# Sheet_1.net
KiCad netlist of a schematic drawn in EasyEDA
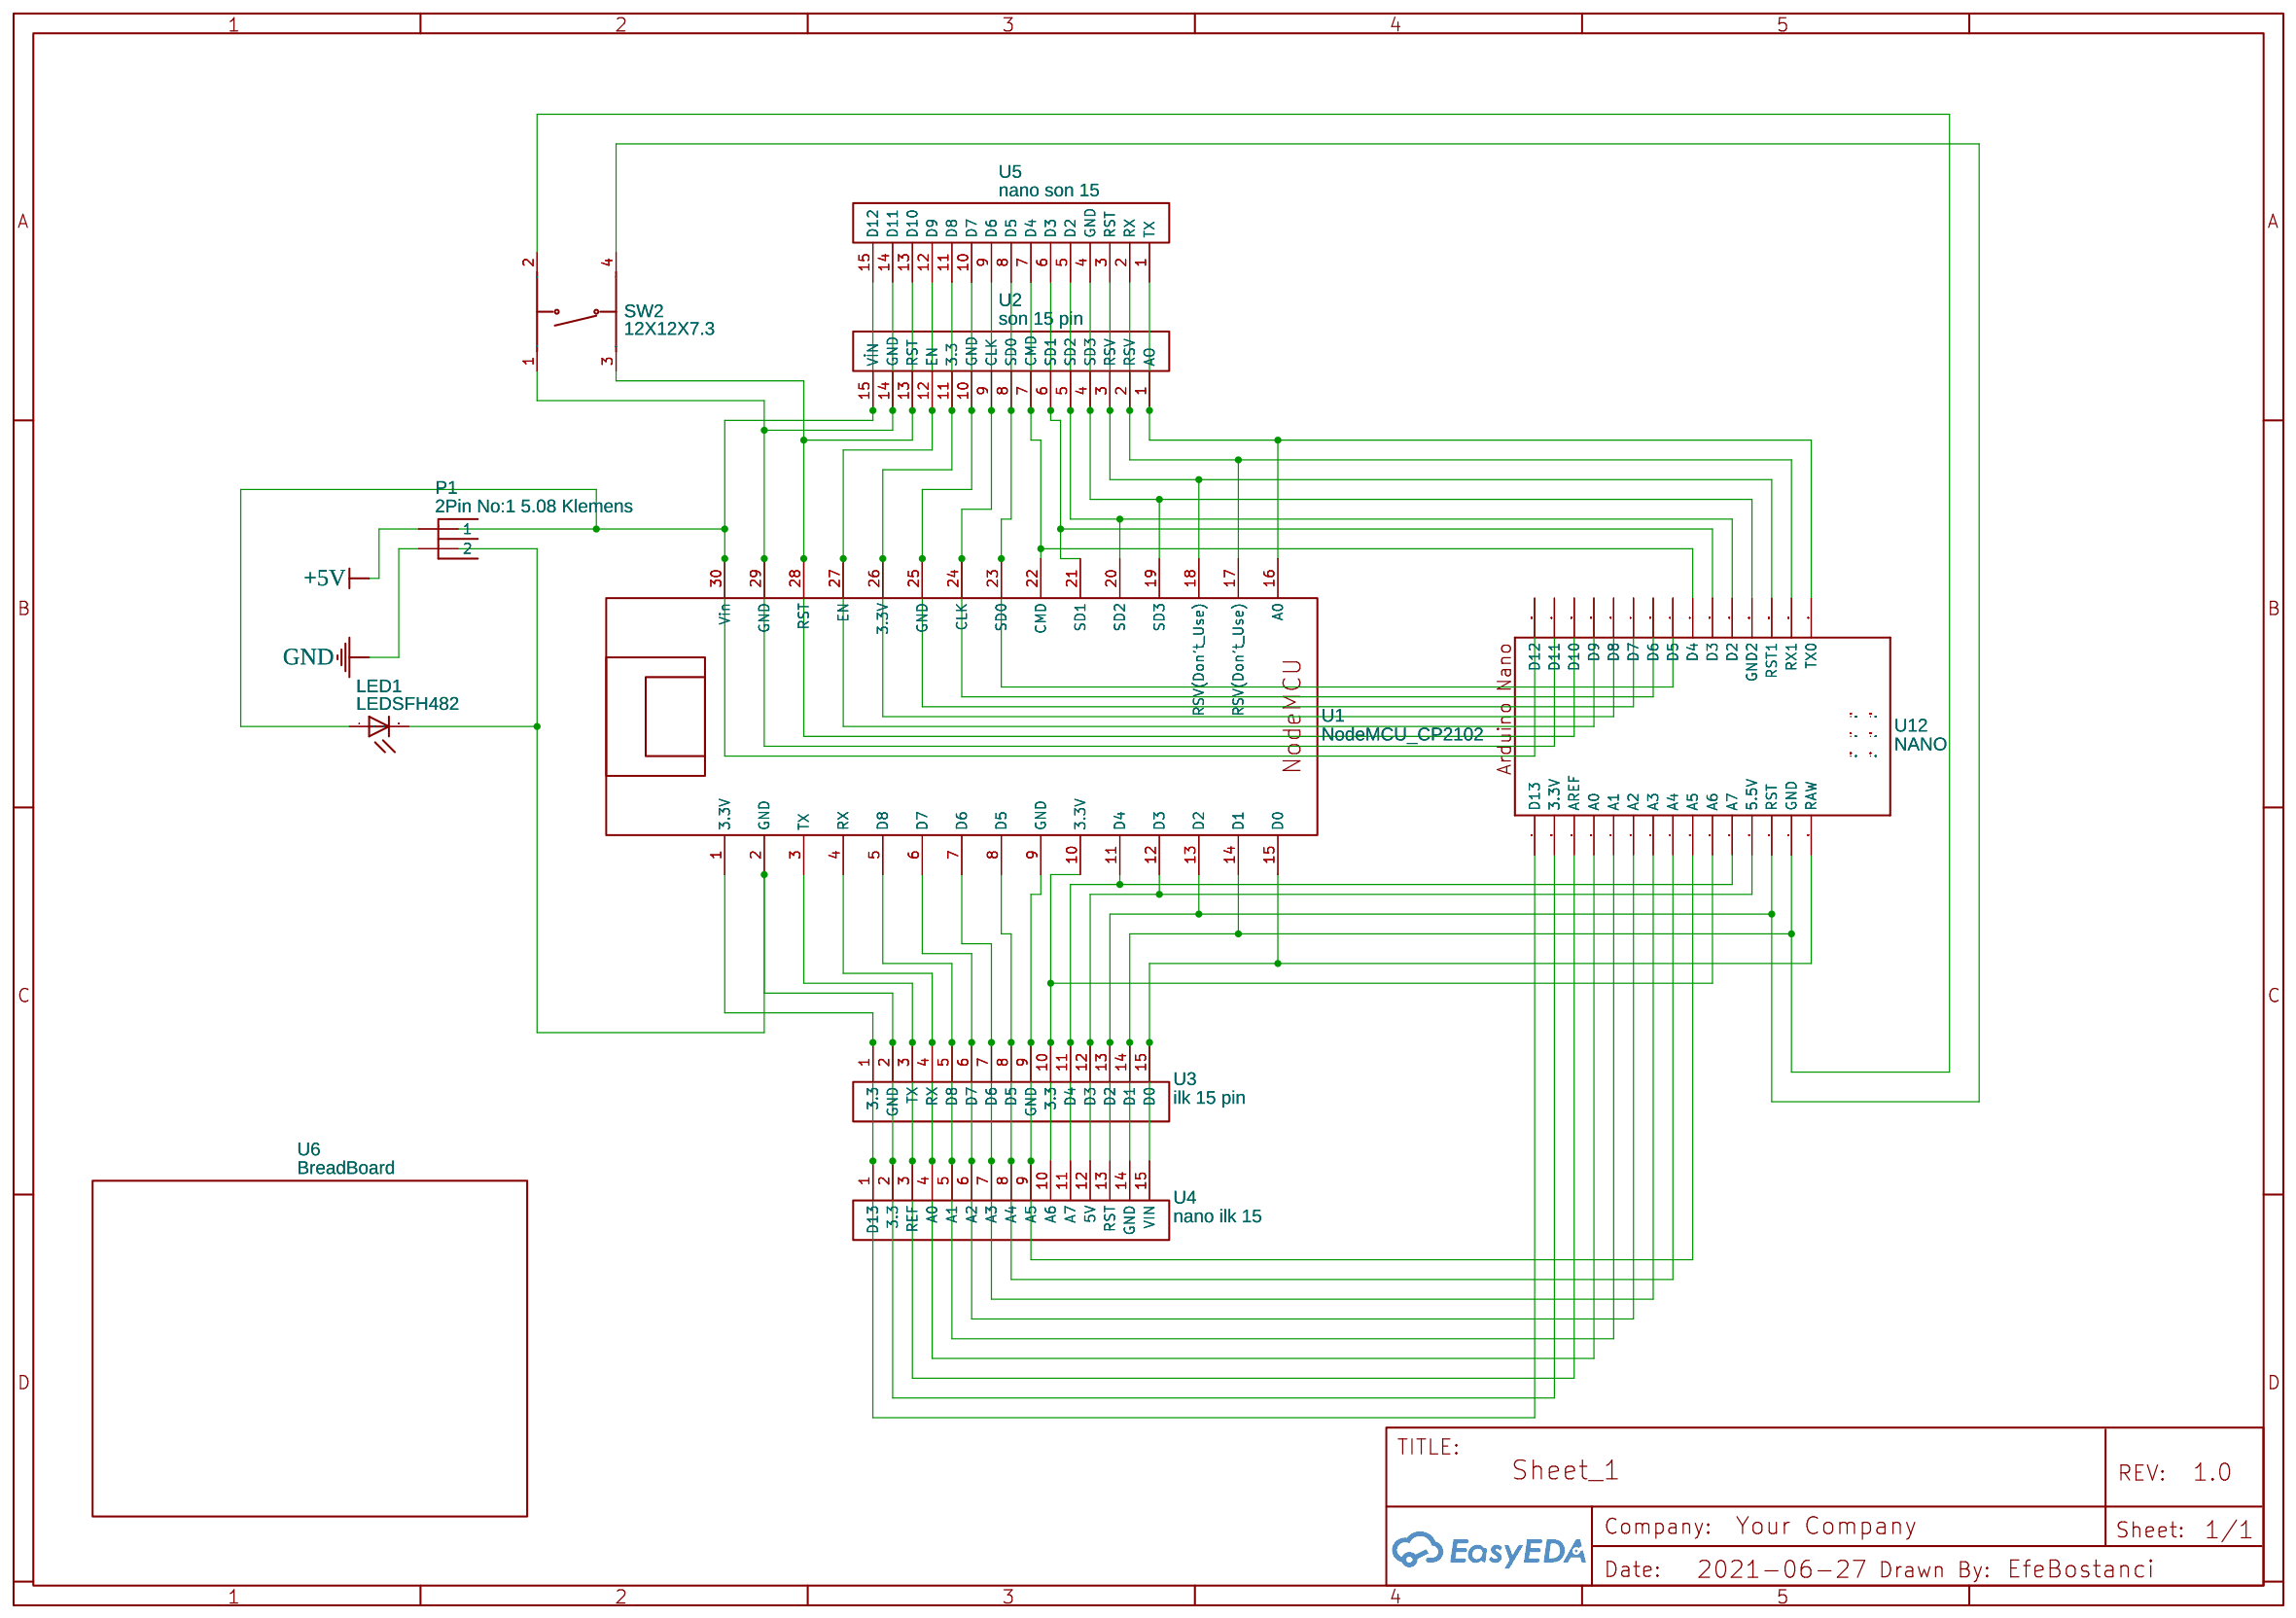
[diagram p0: schematic sheet]

(export (version "E")
  (design (tool "Eeschema 10.0.6"))
  (components
    (comp (ref "LED1") (value "LEDSFH482") (libsource (lib "") (part "LEDSFH482")))
    (comp (ref "P1")
      (value "2Pin No:1 5.08 Klemens")
      (fields (field (name "BOM_Manufacturer Part") "Terminal 2Pol 5,08mm"))
      (libsource (lib "") (part "2Pin No{colon}1 5.08 Klemens"))
    )
    (comp (ref "SW2")
      (value "12X12X7.3")
      (fields (field (name "BOM_Supplier Part") "C10861"))
      (libsource (lib "") (part "12X12X7.3"))
    )
    (comp (ref "U1") (value "NodeMCU_CP2102") (libsource (lib "") (part "NodeMCU_CP2102")))
    (comp (ref "U2") (value "son 15 pin") (libsource (lib "") (part "15 pin_1")))
    (comp (ref "U3") (value "ilk 15 pin") (libsource (lib "") (part "15 pin_3")))
    (comp (ref "U4") (value "nano ilk 15") (libsource (lib "") (part "15 pin")))
    (comp (ref "U5") (value "nano son 15") (libsource (lib "") (part "15 pin_2")))
    (comp (ref "U6") (value "BreadBoard") (libsource (lib "") (part "BreadBoard")))
    (comp (ref "U12") (value "NANO") (libsource (lib "") (part "NANO")))
  )
  (nets
    (net (code "1") (name "+5V") (class "Default")
      (node (ref "P1") (pin "1") (pinfunction "1_1") (pintype "unspecified"))
    )
    (net (code "2") (name "GND") (class "Default")
      (node (ref "P1") (pin "2") (pinfunction "2_2") (pintype "unspecified"))
    )
    (net (code "3") (name "Net-(LED1-C)") (class "Default")
      (node (ref "LED1") (pin "K") (pinfunction "C_K") (pintype "unspecified"))
      (node (ref "U1") (pin "2") (pinfunction "GND_2") (pintype "unspecified"))
      (node (ref "U12") (pin "3.3V") (pinfunction "3.3V_3.3V") (pintype "unspecified"))
      (node (ref "U3") (pin "2") (pinfunction "GND_2") (pintype "unspecified"))
      (node (ref "U4") (pin "2") (pinfunction "3.3_2") (pintype "unspecified"))
    )
    (net (code "4") (name "Net-(U1-A0)") (class "Default")
      (node (ref "U1") (pin "16") (pinfunction "A0_16") (pintype "unspecified"))
      (node (ref "U12") (pin "TX0") (pinfunction "TX0_TX0") (pintype "unspecified"))
      (node (ref "U2") (pin "1") (pinfunction "AO_1") (pintype "unspecified"))
      (node (ref "U5") (pin "1") (pinfunction "TX_1") (pintype "unspecified"))
    )
    (net (code "5") (name "Net-(U1-CLK)") (class "Default")
      (node (ref "U1") (pin "24") (pinfunction "CLK_24") (pintype "unspecified"))
      (node (ref "U12") (pin "D6") (pinfunction "D6_D6") (pintype "unspecified"))
      (node (ref "U2") (pin "9") (pinfunction "CLK_9") (pintype "unspecified"))
      (node (ref "U5") (pin "9") (pinfunction "D6_9") (pintype "unspecified"))
    )
    (net (code "6") (name "Net-(U1-CMD)") (class "Default")
      (node (ref "U1") (pin "22") (pinfunction "CMD_22") (pintype "unspecified"))
      (node (ref "U12") (pin "D4") (pinfunction "D4_D4") (pintype "unspecified"))
      (node (ref "U2") (pin "7") (pinfunction "CMD_7") (pintype "unspecified"))
      (node (ref "U5") (pin "7") (pinfunction "D4_7") (pintype "unspecified"))
    )
    (net (code "7") (name "Net-(U1-D0)") (class "Default")
      (node (ref "U1") (pin "15") (pinfunction "D0_15") (pintype "unspecified"))
      (node (ref "U12") (pin "RAW") (pinfunction "RAW_RAW") (pintype "unspecified"))
      (node (ref "U3") (pin "15") (pinfunction "D0_15") (pintype "unspecified"))
      (node (ref "U4") (pin "15") (pinfunction "VIN_15") (pintype "unspecified"))
    )
    (net (code "8") (name "Net-(U1-D1)") (class "Default")
      (node (ref "SW2") (pin "2") (pinfunction "2_2") (pintype "unspecified"))
      (node (ref "U1") (pin "14") (pinfunction "D1_14") (pintype "unspecified"))
      (node (ref "U12") (pin "GND") (pinfunction "GND_GND") (pintype "unspecified"))
      (node (ref "U3") (pin "14") (pinfunction "D1_14") (pintype "unspecified"))
      (node (ref "U4") (pin "14") (pinfunction "GND_14") (pintype "unspecified"))
    )
    (net (code "9") (name "Net-(U1-D2)") (class "Default")
      (node (ref "SW2") (pin "4") (pinfunction "4_4") (pintype "unspecified"))
      (node (ref "U1") (pin "13") (pinfunction "D2_13") (pintype "unspecified"))
      (node (ref "U12") (pin "RST") (pinfunction "RST_RST") (pintype "unspecified"))
      (node (ref "U3") (pin "13") (pinfunction "D2_13") (pintype "unspecified"))
      (node (ref "U4") (pin "13") (pinfunction "RST_13") (pintype "unspecified"))
    )
    (net (code "10") (name "Net-(U1-D3)") (class "Default")
      (node (ref "U1") (pin "12") (pinfunction "D3_12") (pintype "unspecified"))
      (node (ref "U12") (pin "5V") (pinfunction "5.5V_5V") (pintype "unspecified"))
      (node (ref "U3") (pin "12") (pinfunction "D3_12") (pintype "unspecified"))
      (node (ref "U4") (pin "12") (pinfunction "5V_12") (pintype "unspecified"))
    )
    (net (code "11") (name "Net-(U1-D4)") (class "Default")
      (node (ref "U1") (pin "11") (pinfunction "D4_11") (pintype "unspecified"))
      (node (ref "U12") (pin "A7") (pinfunction "A7_A7") (pintype "unspecified"))
      (node (ref "U3") (pin "11") (pinfunction "D4_11") (pintype "unspecified"))
      (node (ref "U4") (pin "11") (pinfunction "A7_11") (pintype "unspecified"))
    )
    (net (code "12") (name "Net-(U1-D5)") (class "Default")
      (node (ref "U1") (pin "8") (pinfunction "D5_8") (pintype "unspecified"))
      (node (ref "U12") (pin "A4") (pinfunction "A4_A4") (pintype "unspecified"))
      (node (ref "U3") (pin "8") (pinfunction "D5_8") (pintype "unspecified"))
      (node (ref "U4") (pin "8") (pinfunction "A4_8") (pintype "unspecified"))
    )
    (net (code "13") (name "Net-(U1-D6)") (class "Default")
      (node (ref "U1") (pin "7") (pinfunction "D6_7") (pintype "unspecified"))
      (node (ref "U12") (pin "A3") (pinfunction "A3_A3") (pintype "unspecified"))
      (node (ref "U3") (pin "7") (pinfunction "D6_7") (pintype "unspecified"))
      (node (ref "U4") (pin "7") (pinfunction "A3_7") (pintype "unspecified"))
    )
    (net (code "14") (name "Net-(U1-D7)") (class "Default")
      (node (ref "U1") (pin "6") (pinfunction "D7_6") (pintype "unspecified"))
      (node (ref "U12") (pin "A2") (pinfunction "A2_A2") (pintype "unspecified"))
      (node (ref "U3") (pin "6") (pinfunction "D7_6") (pintype "unspecified"))
      (node (ref "U4") (pin "6") (pinfunction "A2_6") (pintype "unspecified"))
    )
    (net (code "15") (name "Net-(U1-D8)") (class "Default")
      (node (ref "U1") (pin "5") (pinfunction "D8_5") (pintype "unspecified"))
      (node (ref "U12") (pin "A1") (pinfunction "A1_A1") (pintype "unspecified"))
      (node (ref "U3") (pin "5") (pinfunction "D8_5") (pintype "unspecified"))
      (node (ref "U4") (pin "5") (pinfunction "A1_5") (pintype "unspecified"))
    )
    (net (code "16") (name "Net-(U1-EN)") (class "Default")
      (node (ref "U1") (pin "27") (pinfunction "EN_27") (pintype "unspecified"))
      (node (ref "U12") (pin "D9") (pinfunction "D9_D9") (pintype "unspecified"))
      (node (ref "U2") (pin "12") (pinfunction "EN_12") (pintype "unspecified"))
      (node (ref "U5") (pin "12") (pinfunction "D9_12") (pintype "unspecified"))
    )
    (net (code "17") (name "Net-(U1-RST)") (class "Default")
      (node (ref "SW2") (pin "3") (pinfunction "3_3") (pintype "unspecified"))
      (node (ref "U1") (pin "28") (pinfunction "RST_28") (pintype "unspecified"))
      (node (ref "U12") (pin "D10") (pinfunction "D10_D10") (pintype "unspecified"))
      (node (ref "U2") (pin "13") (pinfunction "RST_13") (pintype "unspecified"))
      (node (ref "U5") (pin "13") (pinfunction "D10_13") (pintype "unspecified"))
    )
    (net (code "18") (name "Net-(U1-RX)") (class "Default")
      (node (ref "U1") (pin "4") (pinfunction "RX_4") (pintype "unspecified"))
      (node (ref "U12") (pin "A0") (pinfunction "A0_A0") (pintype "unspecified"))
      (node (ref "U3") (pin "4") (pinfunction "RX_4") (pintype "unspecified"))
      (node (ref "U4") (pin "4") (pinfunction "A0_4") (pintype "unspecified"))
    )
    (net (code "19") (name "Net-(U1-SD0)") (class "Default")
      (node (ref "U1") (pin "23") (pinfunction "SD0_23") (pintype "unspecified"))
      (node (ref "U12") (pin "D5") (pinfunction "D5_D5") (pintype "unspecified"))
      (node (ref "U2") (pin "8") (pinfunction "SD0_8") (pintype "unspecified"))
      (node (ref "U5") (pin "8") (pinfunction "D5_8") (pintype "unspecified"))
    )
    (net (code "20") (name "Net-(U1-SD1)") (class "Default")
      (node (ref "U1") (pin "21") (pinfunction "SD1_21") (pintype "unspecified"))
      (node (ref "U12") (pin "D3") (pinfunction "D3_D3") (pintype "unspecified"))
      (node (ref "U2") (pin "6") (pinfunction "SD1_6") (pintype "unspecified"))
      (node (ref "U5") (pin "6") (pinfunction "D3_6") (pintype "unspecified"))
    )
    (net (code "21") (name "Net-(U1-SD2)") (class "Default")
      (node (ref "U1") (pin "20") (pinfunction "SD2_20") (pintype "unspecified"))
      (node (ref "U12") (pin "D2") (pinfunction "D2_D2") (pintype "unspecified"))
      (node (ref "U2") (pin "5") (pinfunction "SD2_5") (pintype "unspecified"))
      (node (ref "U5") (pin "5") (pinfunction "D2_5") (pintype "unspecified"))
    )
    (net (code "22") (name "Net-(U1-SD3)") (class "Default")
      (node (ref "U1") (pin "19") (pinfunction "SD3_19") (pintype "unspecified"))
      (node (ref "U12") (pin "GND1") (pinfunction "GND2_GND1") (pintype "unspecified"))
      (node (ref "U2") (pin "4") (pinfunction "SD3_4") (pintype "unspecified"))
      (node (ref "U5") (pin "4") (pinfunction "GND_4") (pintype "unspecified"))
    )
    (net (code "23") (name "Net-(U1-TX)") (class "Default")
      (node (ref "U1") (pin "3") (pinfunction "TX_3") (pintype "unspecified"))
      (node (ref "U12") (pin "AREF") (pinfunction "AREF_AREF") (pintype "unspecified"))
      (node (ref "U3") (pin "3") (pinfunction "TX_3") (pintype "unspecified"))
      (node (ref "U4") (pin "3") (pinfunction "REF_3") (pintype "unspecified"))
    )
    (net (code "24") (name "Net-(U1-Vin)") (class "Default")
      (node (ref "LED1") (pin "A") (pinfunction "A_A") (pintype "unspecified"))
      (node (ref "U1") (pin "30") (pinfunction "Vin_30") (pintype "unspecified"))
      (node (ref "U12") (pin "D12") (pinfunction "D12_D12") (pintype "unspecified"))
      (node (ref "U2") (pin "15") (pinfunction "VİN_15") (pintype "unspecified"))
      (node (ref "U5") (pin "15") (pinfunction "D12_15") (pintype "unspecified"))
    )
    (net (code "25") (name "Net-(U2-3.3)") (class "Default")
      (node (ref "U1") (pin "26") (pinfunction "3.3V_26") (pintype "unspecified"))
      (node (ref "U12") (pin "D8") (pinfunction "D8_D8") (pintype "unspecified"))
      (node (ref "U2") (pin "11") (pinfunction "3.3_11") (pintype "unspecified"))
      (node (ref "U5") (pin "11") (pinfunction "D8_11") (pintype "unspecified"))
    )
    (net (code "26") (name "Net-(U4-A5)") (class "Default")
      (node (ref "U1") (pin "9") (pinfunction "GND_9") (pintype "unspecified"))
      (node (ref "U12") (pin "A5") (pinfunction "A5_A5") (pintype "unspecified"))
      (node (ref "U3") (pin "9") (pinfunction "GND_9") (pintype "unspecified"))
      (node (ref "U4") (pin "9") (pinfunction "A5_9") (pintype "unspecified"))
    )
    (net (code "27") (name "Net-(U4-A6)") (class "Default")
      (node (ref "U1") (pin "10") (pinfunction "3.3V_10") (pintype "unspecified"))
      (node (ref "U12") (pin "A6") (pinfunction "A6_A6") (pintype "unspecified"))
      (node (ref "U3") (pin "10") (pinfunction "3.3_10") (pintype "unspecified"))
      (node (ref "U4") (pin "10") (pinfunction "A6_10") (pintype "unspecified"))
    )
    (net (code "28") (name "Net-(U4-D13)") (class "Default")
      (node (ref "U1") (pin "1") (pinfunction "3.3V_1") (pintype "unspecified"))
      (node (ref "U12") (pin "D13") (pinfunction "D13_D13") (pintype "unspecified"))
      (node (ref "U3") (pin "1") (pinfunction "3.3_1") (pintype "unspecified"))
      (node (ref "U4") (pin "1") (pinfunction "D13_1") (pintype "unspecified"))
    )
    (net (code "29") (name "Net-(U5-D7)") (class "Default")
      (node (ref "U1") (pin "25") (pinfunction "GND_25") (pintype "unspecified"))
      (node (ref "U12") (pin "D7") (pinfunction "D7_D7") (pintype "unspecified"))
      (node (ref "U2") (pin "10") (pinfunction "GND_10") (pintype "unspecified"))
      (node (ref "U5") (pin "10") (pinfunction "D7_10") (pintype "unspecified"))
    )
    (net (code "30") (name "Net-(U5-D11)") (class "Default")
      (node (ref "SW2") (pin "1") (pinfunction "1_1") (pintype "unspecified"))
      (node (ref "U1") (pin "29") (pinfunction "GND_29") (pintype "unspecified"))
      (node (ref "U12") (pin "D11") (pinfunction "D11_D11") (pintype "unspecified"))
      (node (ref "U2") (pin "14") (pinfunction "GND_14") (pintype "unspecified"))
      (node (ref "U5") (pin "14") (pinfunction "D11_14") (pintype "unspecified"))
    )
    (net (code "31") (name "Net-(U5-RST)") (class "Default")
      (node (ref "U1") (pin "18") (pinfunction "RSV(Don't_Use)_18") (pintype "unspecified"))
      (node (ref "U12") (pin "RST1") (pinfunction "RST1_RST1") (pintype "unspecified"))
      (node (ref "U2") (pin "3") (pinfunction "RSV_3") (pintype "unspecified"))
      (node (ref "U5") (pin "3") (pinfunction "RST_3") (pintype "unspecified"))
    )
    (net (code "32") (name "Net-(U5-RX)") (class "Default")
      (node (ref "U1") (pin "17") (pinfunction "RSV(Don't_Use)_17") (pintype "unspecified"))
      (node (ref "U12") (pin "RX1") (pinfunction "RX1_RX1") (pintype "unspecified"))
      (node (ref "U2") (pin "2") (pinfunction "RSV_2") (pintype "unspecified"))
      (node (ref "U5") (pin "2") (pinfunction "RX_2") (pintype "unspecified"))
    )
    (net (code "33") (name "unconnected-(U12-PadICSP1)") (class "Default")
      (node (ref "U12") (pin "ICSP1") (pinfunction "ICSP1_ICSP1") (pintype "unspecified"))
    )
    (net (code "34") (name "unconnected-(U12-PadICSP2)") (class "Default")
      (node (ref "U12") (pin "ICSP2") (pinfunction "ICSP2_ICSP2") (pintype "unspecified"))
    )
    (net (code "35") (name "unconnected-(U12-PadICSP3)") (class "Default")
      (node (ref "U12") (pin "ICSP3") (pinfunction "ICSP3_ICSP3") (pintype "unspecified"))
    )
    (net (code "36") (name "unconnected-(U12-PadICSP4)") (class "Default")
      (node (ref "U12") (pin "ICSP4") (pinfunction "ICSP4_ICSP4") (pintype "unspecified"))
    )
    (net (code "37") (name "unconnected-(U12-PadICSP5)") (class "Default")
      (node (ref "U12") (pin "ICSP5") (pinfunction "ICSP5_ICSP5") (pintype "unspecified"))
    )
    (net (code "38") (name "unconnected-(U12-PadICSP6)") (class "Default")
      (node (ref "U12") (pin "ICSP6") (pinfunction "ICSP6_ICSP6") (pintype "unspecified"))
    )
  )
)
